# CajitaAbierta.net
KiCad netlist of a schematic drawn in EAGLE
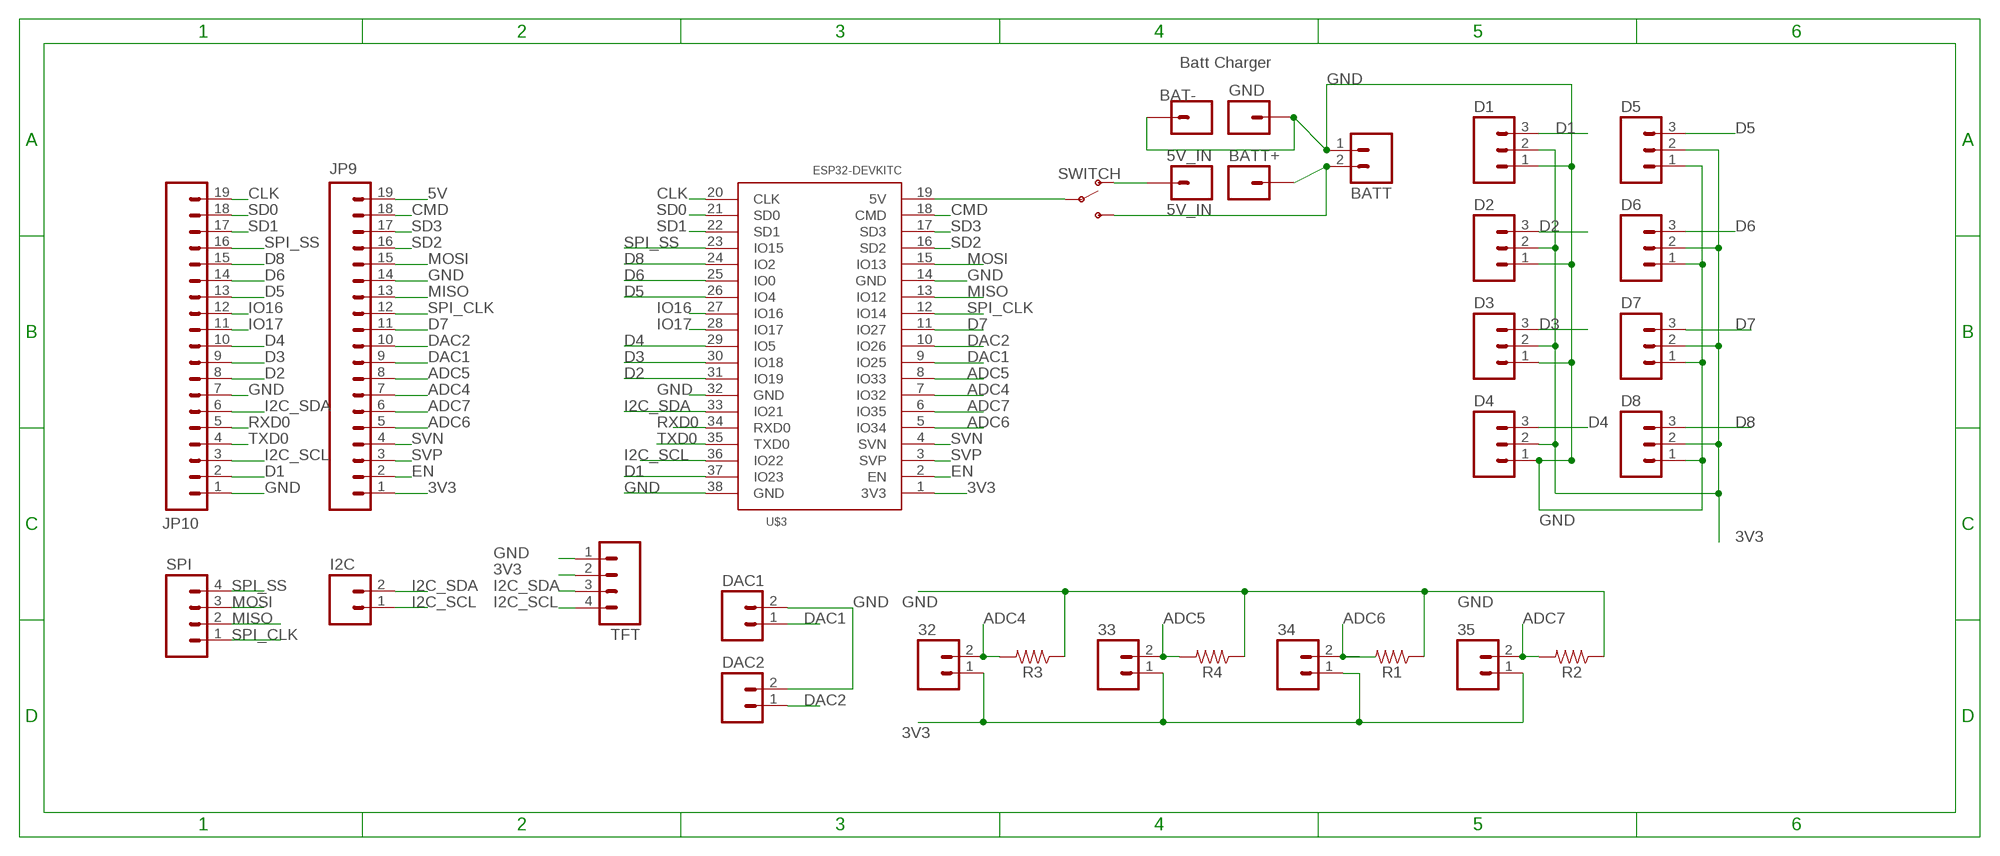
[diagram p0: schematic, sheet 1]

(export (version "E")
  (design (tool "Eeschema 10.0.6"))
  (components
    (comp (ref "5V_IN")
      (value "5V_IN")
      (footprint "eagle-import:1X01")
      (libsource (lib "eagle-import") (part "M01PTH"))
    )
    (comp (ref "32")
      (value "M02PTH")
      (footprint "eagle-import:1X02")
      (libsource (lib "eagle-import") (part "SparkFun-Connectors_6242394_M02PTH"))
    )
    (comp (ref "33")
      (value "M02PTH")
      (footprint "eagle-import:1X02")
      (libsource (lib "eagle-import") (part "SparkFun-Connectors_6242394_M02PTH"))
    )
    (comp (ref "34")
      (value "M02PTH")
      (footprint "eagle-import:1X02")
      (libsource (lib "eagle-import") (part "SparkFun-Connectors_6242394_M02PTH"))
    )
    (comp (ref "35")
      (value "M02PTH")
      (footprint "eagle-import:1X02")
      (libsource (lib "eagle-import") (part "SparkFun-Connectors_6242394_M02PTH"))
    )
    (comp (ref "BAT-")
      (value "M01PTH")
      (footprint "eagle-import:1X01")
      (libsource (lib "eagle-import") (part "M01PTH"))
    )
    (comp (ref "BATT")
      (value "M02LOCK_LONGPADS")
      (footprint "eagle-import:1X02_LOCK_LONGPADS")
      (libsource (lib "eagle-import") (part "M02LOCK_LONGPADS"))
    )
    (comp (ref "BATT+")
      (value "M01PTH")
      (footprint "eagle-import:1X01")
      (libsource (lib "eagle-import") (part "M01PTH"))
    )
    (comp (ref "D1")
      (value "M03LOCK_LONGPADS")
      (footprint "eagle-import:1X03_LOCK_LONGPADS")
      (libsource (lib "eagle-import") (part "M03LOCK_LONGPADS"))
    )
    (comp (ref "D2")
      (value "M03LOCK_LONGPADS")
      (footprint "eagle-import:1X03_LOCK_LONGPADS")
      (libsource (lib "eagle-import") (part "M03LOCK_LONGPADS"))
    )
    (comp (ref "D3")
      (value "M03LOCK_LONGPADS")
      (footprint "eagle-import:1X03_LOCK_LONGPADS")
      (libsource (lib "eagle-import") (part "M03LOCK_LONGPADS"))
    )
    (comp (ref "D4")
      (value "M03LOCK_LONGPADS")
      (footprint "eagle-import:1X03_LOCK_LONGPADS")
      (libsource (lib "eagle-import") (part "M03LOCK_LONGPADS"))
    )
    (comp (ref "D5")
      (value "M03LOCK_LONGPADS")
      (footprint "eagle-import:1X03_LOCK_LONGPADS")
      (libsource (lib "eagle-import") (part "M03LOCK_LONGPADS"))
    )
    (comp (ref "D6")
      (value "M03LOCK_LONGPADS")
      (footprint "eagle-import:1X03_LOCK_LONGPADS")
      (libsource (lib "eagle-import") (part "M03LOCK_LONGPADS"))
    )
    (comp (ref "D7")
      (value "M03LOCK_LONGPADS")
      (footprint "eagle-import:1X03_LOCK_LONGPADS")
      (libsource (lib "eagle-import") (part "M03LOCK_LONGPADS"))
    )
    (comp (ref "D8")
      (value "M03LOCK_LONGPADS")
      (footprint "eagle-import:1X03_LOCK_LONGPADS")
      (libsource (lib "eagle-import") (part "M03LOCK_LONGPADS"))
    )
    (comp (ref "DAC1")
      (value "M02PTH")
      (footprint "eagle-import:1X02")
      (libsource (lib "eagle-import") (part "SparkFun-Connectors_6242394_M02PTH"))
    )
    (comp (ref "DAC2")
      (value "M02PTH")
      (footprint "eagle-import:1X02")
      (libsource (lib "eagle-import") (part "SparkFun-Connectors_6242394_M02PTH"))
    )
    (comp (ref "GND")
      (value "Batt Charger")
      (footprint "eagle-import:1X01")
      (libsource (lib "eagle-import") (part "M01PTH"))
    )
    (comp (ref "I2C")
      (value "M02PTH")
      (footprint "eagle-import:1X02")
      (libsource (lib "eagle-import") (part "SparkFun-Connectors_6242394_M02PTH"))
    )
    (comp (ref "JP9")
      (value "M191X19")
      (footprint "eagle-import:1X19")
      (libsource (lib "eagle-import") (part "M191X19"))
    )
    (comp (ref "JP10")
      (value "M191X19")
      (footprint "eagle-import:1X19")
      (libsource (lib "eagle-import") (part "M191X19"))
    )
    (comp (ref "R1")
      (value "RESISTOR1206")
      (footprint "eagle-import:1206")
      (libsource (lib "eagle-import") (part "RESISTOR1206"))
    )
    (comp (ref "R2")
      (value "RESISTOR1206")
      (footprint "eagle-import:1206")
      (libsource (lib "eagle-import") (part "RESISTOR1206"))
    )
    (comp (ref "R3")
      (value "RESISTOR1206")
      (footprint "eagle-import:1206")
      (libsource (lib "eagle-import") (part "RESISTOR1206"))
    )
    (comp (ref "R4")
      (value "RESISTOR1206")
      (footprint "eagle-import:1206")
      (libsource (lib "eagle-import") (part "RESISTOR1206"))
    )
    (comp (ref "SPI")
      (value "M04PTH")
      (footprint "eagle-import:1X04")
      (libsource (lib "eagle-import") (part "M04PTH"))
    )
    (comp (ref "SWITCH")
      (value "SWITCH-SPDT-SMD-RIGHT-ANGLE")
      (footprint "eagle-import:SWITCH_SPST_SMD_A")
      (libsource (lib "eagle-import") (part "SWITCH-SPDT-SMD-RIGHT-ANGLE"))
    )
    (comp (ref "TFT")
      (value "M04PTH")
      (footprint "eagle-import:1X04")
      (libsource (lib "eagle-import") (part "M04PTH"))
    )
    (comp (ref "U$3")
      (value "ESP32DEVKITC")
      (footprint "eagle-import:ESP32-DEVKITC")
      (libsource (lib "eagle-import") (part "ESP32DEVKITC"))
    )
  )
  (nets
    (net (code "1") (name "/3V3") (class "Default")
      (node (ref "32") (pin "1") (pinfunction "1_1") (pintype "passive"))
      (node (ref "33") (pin "1") (pinfunction "1_1") (pintype "passive"))
      (node (ref "34") (pin "1") (pinfunction "1_1") (pintype "passive"))
      (node (ref "35") (pin "1") (pinfunction "1_1") (pintype "passive"))
      (node (ref "D1") (pin "2") (pinfunction "2_2") (pintype "passive"))
      (node (ref "D2") (pin "2") (pinfunction "2_2") (pintype "passive"))
      (node (ref "D3") (pin "2") (pinfunction "2_2") (pintype "passive"))
      (node (ref "D4") (pin "2") (pinfunction "2_2") (pintype "passive"))
      (node (ref "D5") (pin "2") (pinfunction "2_2") (pintype "passive"))
      (node (ref "D6") (pin "2") (pinfunction "2_2") (pintype "passive"))
      (node (ref "D7") (pin "2") (pinfunction "2_2") (pintype "passive"))
      (node (ref "D8") (pin "2") (pinfunction "2_2") (pintype "passive"))
      (node (ref "JP9") (pin "1") (pinfunction "1_1") (pintype "passive"))
      (node (ref "TFT") (pin "2") (pinfunction "2_2") (pintype "passive"))
      (node (ref "U$3") (pin "1") (pinfunction "3V3_1") (pintype "bidirectional"))
    )
    (net (code "2") (name "/5V") (class "Default")
      (node (ref "JP9") (pin "19") (pinfunction "19_19") (pintype "passive"))
      (node (ref "SWITCH") (pin "2") (pinfunction "P_2") (pintype "passive"))
      (node (ref "U$3") (pin "19") (pinfunction "5V_19") (pintype "bidirectional"))
    )
    (net (code "3") (name "/ADC4") (class "Default")
      (node (ref "32") (pin "2") (pinfunction "2_2") (pintype "passive"))
      (node (ref "JP9") (pin "7") (pinfunction "7_7") (pintype "passive"))
      (node (ref "R3") (pin "2") (pinfunction "2_2") (pintype "passive"))
      (node (ref "U$3") (pin "7") (pinfunction "IO32_7") (pintype "bidirectional"))
    )
    (net (code "4") (name "/ADC5") (class "Default")
      (node (ref "33") (pin "2") (pinfunction "2_2") (pintype "passive"))
      (node (ref "JP9") (pin "8") (pinfunction "8_8") (pintype "passive"))
      (node (ref "R4") (pin "2") (pinfunction "2_2") (pintype "passive"))
      (node (ref "U$3") (pin "8") (pinfunction "IO33_8") (pintype "bidirectional"))
    )
    (net (code "5") (name "/ADC6") (class "Default")
      (node (ref "34") (pin "2") (pinfunction "2_2") (pintype "passive"))
      (node (ref "JP9") (pin "5") (pinfunction "5_5") (pintype "passive"))
      (node (ref "R1") (pin "2") (pinfunction "2_2") (pintype "passive"))
      (node (ref "U$3") (pin "5") (pinfunction "IO34_5") (pintype "bidirectional"))
    )
    (net (code "6") (name "/ADC7") (class "Default")
      (node (ref "35") (pin "2") (pinfunction "2_2") (pintype "passive"))
      (node (ref "JP9") (pin "6") (pinfunction "6_6") (pintype "passive"))
      (node (ref "R2") (pin "2") (pinfunction "2_2") (pintype "passive"))
      (node (ref "U$3") (pin "6") (pinfunction "IO35_6") (pintype "bidirectional"))
    )
    (net (code "7") (name "/CLK") (class "Default")
      (node (ref "JP10") (pin "19") (pinfunction "19_19") (pintype "passive"))
      (node (ref "U$3") (pin "20") (pinfunction "CLK_20") (pintype "bidirectional"))
    )
    (net (code "8") (name "/CMD") (class "Default")
      (node (ref "JP9") (pin "18") (pinfunction "18_18") (pintype "passive"))
      (node (ref "U$3") (pin "18") (pinfunction "CMD_18") (pintype "bidirectional"))
    )
    (net (code "9") (name "/D1") (class "Default")
      (node (ref "D1") (pin "3") (pinfunction "3_3") (pintype "passive"))
      (node (ref "JP10") (pin "2") (pinfunction "2_2") (pintype "passive"))
      (node (ref "U$3") (pin "37") (pinfunction "IO23_37") (pintype "bidirectional"))
    )
    (net (code "10") (name "/D2") (class "Default")
      (node (ref "D2") (pin "3") (pinfunction "3_3") (pintype "passive"))
      (node (ref "JP10") (pin "8") (pinfunction "8_8") (pintype "passive"))
      (node (ref "U$3") (pin "31") (pinfunction "IO19_31") (pintype "bidirectional"))
    )
    (net (code "11") (name "/D3") (class "Default")
      (node (ref "D3") (pin "3") (pinfunction "3_3") (pintype "passive"))
      (node (ref "JP10") (pin "9") (pinfunction "9_9") (pintype "passive"))
      (node (ref "U$3") (pin "30") (pinfunction "IO18_30") (pintype "bidirectional"))
    )
    (net (code "12") (name "/D4") (class "Default")
      (node (ref "D4") (pin "3") (pinfunction "3_3") (pintype "passive"))
      (node (ref "JP10") (pin "10") (pinfunction "10_10") (pintype "passive"))
      (node (ref "U$3") (pin "29") (pinfunction "IO5_29") (pintype "bidirectional"))
    )
    (net (code "13") (name "/D5") (class "Default")
      (node (ref "D5") (pin "3") (pinfunction "3_3") (pintype "passive"))
      (node (ref "JP10") (pin "13") (pinfunction "13_13") (pintype "passive"))
      (node (ref "U$3") (pin "26") (pinfunction "IO4_26") (pintype "bidirectional"))
    )
    (net (code "14") (name "/D6") (class "Default")
      (node (ref "D6") (pin "3") (pinfunction "3_3") (pintype "passive"))
      (node (ref "JP10") (pin "14") (pinfunction "14_14") (pintype "passive"))
      (node (ref "U$3") (pin "25") (pinfunction "IO0_25") (pintype "bidirectional"))
    )
    (net (code "15") (name "/D7") (class "Default")
      (node (ref "D7") (pin "3") (pinfunction "3_3") (pintype "passive"))
      (node (ref "JP9") (pin "11") (pinfunction "11_11") (pintype "passive"))
      (node (ref "U$3") (pin "11") (pinfunction "IO27_11") (pintype "bidirectional"))
    )
    (net (code "16") (name "/D8") (class "Default")
      (node (ref "D8") (pin "3") (pinfunction "3_3") (pintype "passive"))
      (node (ref "JP10") (pin "15") (pinfunction "15_15") (pintype "passive"))
      (node (ref "U$3") (pin "24") (pinfunction "IO2_24") (pintype "bidirectional"))
    )
    (net (code "17") (name "/DAC1") (class "Default")
      (node (ref "DAC1") (pin "1") (pinfunction "1_1") (pintype "passive"))
      (node (ref "JP9") (pin "9") (pinfunction "9_9") (pintype "passive"))
      (node (ref "U$3") (pin "9") (pinfunction "IO25_9") (pintype "bidirectional"))
    )
    (net (code "18") (name "/DAC2") (class "Default")
      (node (ref "DAC2") (pin "1") (pinfunction "1_1") (pintype "passive"))
      (node (ref "JP9") (pin "10") (pinfunction "10_10") (pintype "passive"))
      (node (ref "U$3") (pin "10") (pinfunction "IO26_10") (pintype "bidirectional"))
    )
    (net (code "19") (name "/EN") (class "Default")
      (node (ref "JP9") (pin "2") (pinfunction "2_2") (pintype "passive"))
      (node (ref "U$3") (pin "2") (pinfunction "EN_2") (pintype "bidirectional"))
    )
    (net (code "20") (name "/GND") (class "Default")
      (node (ref "BAT-") (pin "1") (pinfunction "1_1") (pintype "passive"))
      (node (ref "BATT") (pin "1") (pinfunction "1_1") (pintype "passive"))
      (node (ref "D1") (pin "1") (pinfunction "1_1") (pintype "passive"))
      (node (ref "D2") (pin "1") (pinfunction "1_1") (pintype "passive"))
      (node (ref "D3") (pin "1") (pinfunction "1_1") (pintype "passive"))
      (node (ref "D4") (pin "1") (pinfunction "1_1") (pintype "passive"))
      (node (ref "D5") (pin "1") (pinfunction "1_1") (pintype "passive"))
      (node (ref "D6") (pin "1") (pinfunction "1_1") (pintype "passive"))
      (node (ref "D7") (pin "1") (pinfunction "1_1") (pintype "passive"))
      (node (ref "D8") (pin "1") (pinfunction "1_1") (pintype "passive"))
      (node (ref "DAC1") (pin "2") (pinfunction "2_2") (pintype "passive"))
      (node (ref "DAC2") (pin "2") (pinfunction "2_2") (pintype "passive"))
      (node (ref "GND") (pin "1") (pinfunction "1_1") (pintype "passive"))
      (node (ref "JP10") (pin "1") (pinfunction "1_1") (pintype "passive"))
      (node (ref "JP10") (pin "7") (pinfunction "7_7") (pintype "passive"))
      (node (ref "JP9") (pin "14") (pinfunction "14_14") (pintype "passive"))
      (node (ref "R1") (pin "1") (pinfunction "1_1") (pintype "passive"))
      (node (ref "R2") (pin "1") (pinfunction "1_1") (pintype "passive"))
      (node (ref "R3") (pin "1") (pinfunction "1_1") (pintype "passive"))
      (node (ref "R4") (pin "1") (pinfunction "1_1") (pintype "passive"))
      (node (ref "TFT") (pin "1") (pinfunction "1_1") (pintype "passive"))
      (node (ref "U$3") (pin "14") (pinfunction "GND_14") (pintype "bidirectional"))
      (node (ref "U$3") (pin "32") (pinfunction "GND_32") (pintype "bidirectional"))
      (node (ref "U$3") (pin "38") (pinfunction "GND_38") (pintype "bidirectional"))
    )
    (net (code "21") (name "/I2C_SCL") (class "Default")
      (node (ref "I2C") (pin "1") (pinfunction "1_1") (pintype "passive"))
      (node (ref "JP10") (pin "3") (pinfunction "3_3") (pintype "passive"))
      (node (ref "TFT") (pin "4") (pinfunction "4_4") (pintype "passive"))
      (node (ref "U$3") (pin "36") (pinfunction "IO22_36") (pintype "bidirectional"))
    )
    (net (code "22") (name "/I2C_SDA") (class "Default")
      (node (ref "I2C") (pin "2") (pinfunction "2_2") (pintype "passive"))
      (node (ref "JP10") (pin "6") (pinfunction "6_6") (pintype "passive"))
      (node (ref "TFT") (pin "3") (pinfunction "3_3") (pintype "passive"))
      (node (ref "U$3") (pin "33") (pinfunction "IO21_33") (pintype "bidirectional"))
    )
    (net (code "23") (name "/IO16") (class "Default")
      (node (ref "JP10") (pin "12") (pinfunction "12_12") (pintype "passive"))
      (node (ref "U$3") (pin "27") (pinfunction "IO16_27") (pintype "bidirectional"))
    )
    (net (code "24") (name "/IO17") (class "Default")
      (node (ref "JP10") (pin "11") (pinfunction "11_11") (pintype "passive"))
      (node (ref "U$3") (pin "28") (pinfunction "IO17_28") (pintype "bidirectional"))
    )
    (net (code "25") (name "/MISO") (class "Default")
      (node (ref "JP9") (pin "13") (pinfunction "13_13") (pintype "passive"))
      (node (ref "SPI") (pin "2") (pinfunction "2_2") (pintype "passive"))
      (node (ref "U$3") (pin "13") (pinfunction "IO12_13") (pintype "bidirectional"))
    )
    (net (code "26") (name "/MOSI") (class "Default")
      (node (ref "JP9") (pin "15") (pinfunction "15_15") (pintype "passive"))
      (node (ref "SPI") (pin "3") (pinfunction "3_3") (pintype "passive"))
      (node (ref "U$3") (pin "15") (pinfunction "IO13_15") (pintype "bidirectional"))
    )
    (net (code "27") (name "/RXD0") (class "Default")
      (node (ref "JP10") (pin "5") (pinfunction "5_5") (pintype "passive"))
      (node (ref "U$3") (pin "34") (pinfunction "RXD0_34") (pintype "bidirectional"))
    )
    (net (code "28") (name "/SD0") (class "Default")
      (node (ref "JP10") (pin "18") (pinfunction "18_18") (pintype "passive"))
      (node (ref "U$3") (pin "21") (pinfunction "SD0_21") (pintype "bidirectional"))
    )
    (net (code "29") (name "/SD1") (class "Default")
      (node (ref "JP10") (pin "17") (pinfunction "17_17") (pintype "passive"))
      (node (ref "U$3") (pin "22") (pinfunction "SD1_22") (pintype "bidirectional"))
    )
    (net (code "30") (name "/SD2") (class "Default")
      (node (ref "JP9") (pin "16") (pinfunction "16_16") (pintype "passive"))
      (node (ref "U$3") (pin "16") (pinfunction "SD2_16") (pintype "bidirectional"))
    )
    (net (code "31") (name "/SD3") (class "Default")
      (node (ref "JP9") (pin "17") (pinfunction "17_17") (pintype "passive"))
      (node (ref "U$3") (pin "17") (pinfunction "SD3_17") (pintype "bidirectional"))
    )
    (net (code "32") (name "/SPI_CLK") (class "Default")
      (node (ref "JP9") (pin "12") (pinfunction "12_12") (pintype "passive"))
      (node (ref "SPI") (pin "1") (pinfunction "1_1") (pintype "passive"))
      (node (ref "U$3") (pin "12") (pinfunction "IO14_12") (pintype "bidirectional"))
    )
    (net (code "33") (name "/SPI_SS") (class "Default")
      (node (ref "JP10") (pin "16") (pinfunction "16_16") (pintype "passive"))
      (node (ref "SPI") (pin "4") (pinfunction "4_4") (pintype "passive"))
      (node (ref "U$3") (pin "23") (pinfunction "IO15_23") (pintype "bidirectional"))
    )
    (net (code "34") (name "/SVN") (class "Default")
      (node (ref "JP9") (pin "4") (pinfunction "4_4") (pintype "passive"))
      (node (ref "U$3") (pin "4") (pinfunction "SVN_4") (pintype "bidirectional"))
    )
    (net (code "35") (name "/SVP") (class "Default")
      (node (ref "JP9") (pin "3") (pinfunction "3_3") (pintype "passive"))
      (node (ref "U$3") (pin "3") (pinfunction "SVP_3") (pintype "bidirectional"))
    )
    (net (code "36") (name "/TXD0") (class "Default")
      (node (ref "JP10") (pin "4") (pinfunction "4_4") (pintype "passive"))
      (node (ref "U$3") (pin "35") (pinfunction "TXD0_35") (pintype "bidirectional"))
    )
    (net (code "37") (name "Net-(SWITCH-O)") (class "Default")
      (node (ref "5V_IN") (pin "1") (pinfunction "1_1") (pintype "passive"))
      (node (ref "SWITCH") (pin "1") (pinfunction "O_1") (pintype "passive"))
    )
    (net (code "38") (name "Net-(SWITCH-S)") (class "Default")
      (node (ref "BATT") (pin "2") (pinfunction "2_2") (pintype "passive"))
      (node (ref "BATT+") (pin "1") (pinfunction "1_1") (pintype "passive"))
      (node (ref "SWITCH") (pin "3") (pinfunction "S_3") (pintype "passive"))
    )
  )
)
